# HCPL-7840.net
KiCad netlist of a schematic drawn in EAGLE
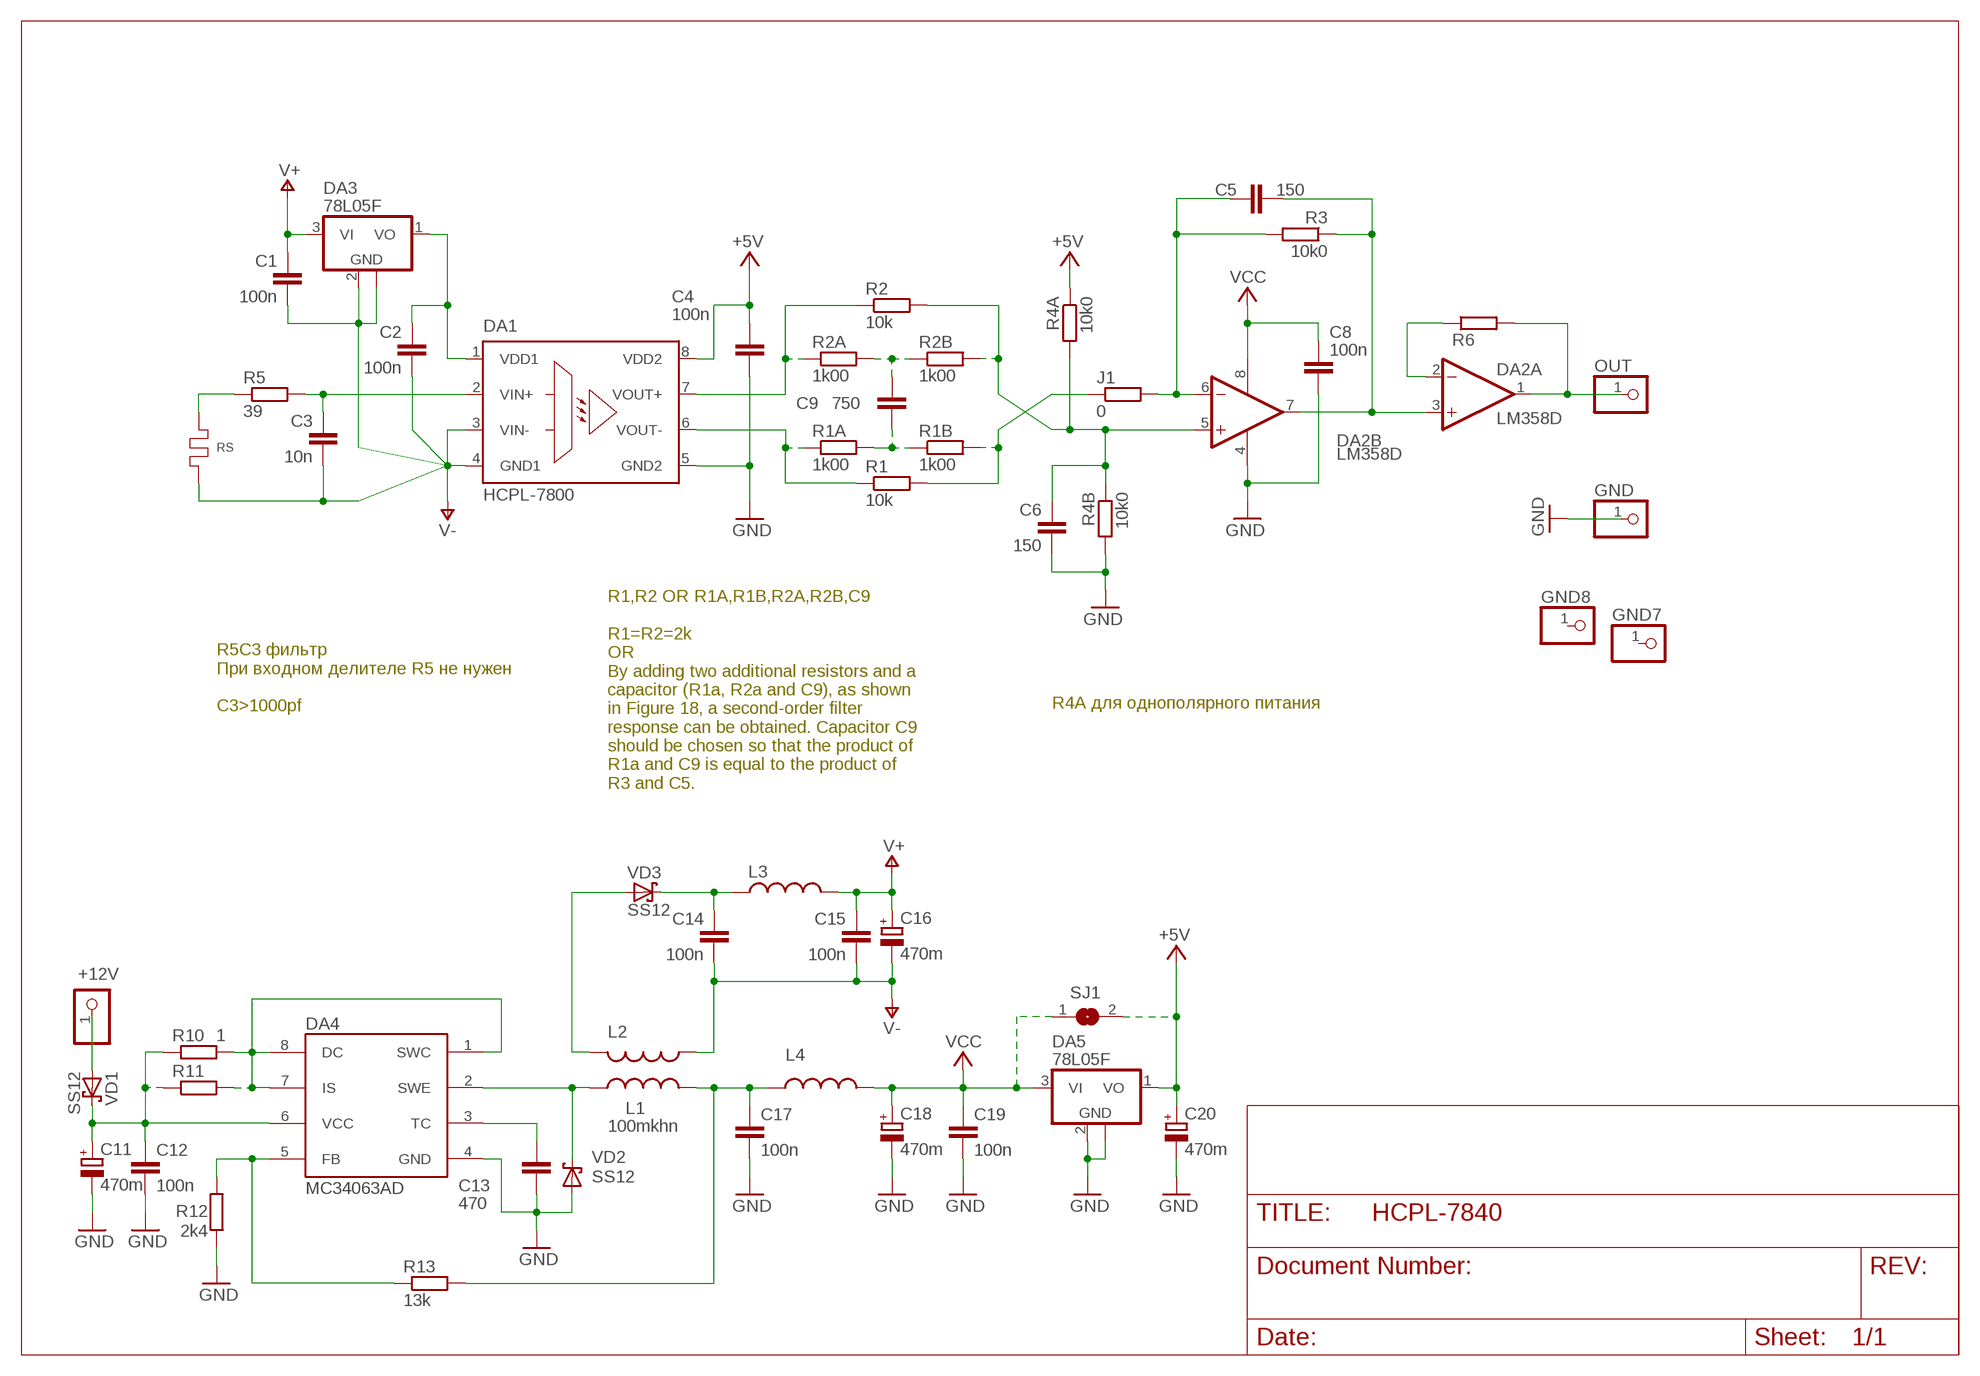
[diagram p0: schematic, sheet 1]

(export (version "E")
  (design (tool "Eeschema 10.0.6"))
  (components
    (comp (ref "+12V")
      (value "PINHD-1X1")
      (footprint "eagle-import:1X01")
      (libsource (lib "eagle-import") (part "PINHD-1X1"))
    )
    (comp (ref "C1")
      (value "100n")
      (footprint "eagle-import:C0805")
      (libsource (lib "eagle-import") (part "C-EUC0805"))
    )
    (comp (ref "C2")
      (value "100n")
      (footprint "eagle-import:C075-032X103")
      (libsource (lib "eagle-import") (part "C-EU075-032X103"))
    )
    (comp (ref "C3")
      (value "10n")
      (footprint "eagle-import:C0805")
      (libsource (lib "eagle-import") (part "C-EUC0805"))
    )
    (comp (ref "C4")
      (value "100n")
      (footprint "eagle-import:C075-032X103")
      (libsource (lib "eagle-import") (part "C-EU075-032X103"))
    )
    (comp (ref "C5")
      (value "150")
      (footprint "eagle-import:C0805")
      (libsource (lib "eagle-import") (part "C-EUC0805"))
    )
    (comp (ref "C6")
      (value "150")
      (footprint "eagle-import:C0805")
      (libsource (lib "eagle-import") (part "C-EUC0805"))
    )
    (comp (ref "C8")
      (value "100n")
      (footprint "eagle-import:C075-032X103")
      (libsource (lib "eagle-import") (part "C-EU075-032X103"))
    )
    (comp (ref "C9")
      (value "750")
      (footprint "eagle-import:C0805")
      (libsource (lib "eagle-import") (part "C-EUC0805"))
    )
    (comp (ref "C11")
      (value "470m")
      (footprint "eagle-import:E2,5-5")
      (libsource (lib "eagle-import") (part "CPOL-EUE2.5-5"))
    )
    (comp (ref "C12")
      (value "100n")
      (footprint "eagle-import:C0805")
      (libsource (lib "eagle-import") (part "C-EUC0805"))
    )
    (comp (ref "C13")
      (value "470")
      (footprint "eagle-import:C0805")
      (libsource (lib "eagle-import") (part "C-EUC0805"))
    )
    (comp (ref "C14")
      (value "100n")
      (footprint "eagle-import:C0805")
      (libsource (lib "eagle-import") (part "C-EUC0805"))
    )
    (comp (ref "C15")
      (value "100n")
      (footprint "eagle-import:C0805")
      (libsource (lib "eagle-import") (part "C-EUC0805"))
    )
    (comp (ref "C16")
      (value "470m")
      (footprint "eagle-import:E2,5-5")
      (libsource (lib "eagle-import") (part "CPOL-EUE2.5-5"))
    )
    (comp (ref "C17")
      (value "100n")
      (footprint "eagle-import:C0805")
      (libsource (lib "eagle-import") (part "C-EUC0805"))
    )
    (comp (ref "C18")
      (value "470m")
      (footprint "eagle-import:E2,5-5")
      (libsource (lib "eagle-import") (part "CPOL-EUE2.5-5"))
    )
    (comp (ref "C19")
      (value "100n")
      (footprint "eagle-import:C0805")
      (libsource (lib "eagle-import") (part "C-EUC0805"))
    )
    (comp (ref "C20")
      (value "470m")
      (footprint "eagle-import:E2,5-5")
      (libsource (lib "eagle-import") (part "CPOL-EUE2.5-5"))
    )
    (comp (ref "DA1")
      (value "HCPL-7800")
      (footprint "eagle-import:DIL08")
      (fields (field (name "MPN") "HCPL-7800A#500"))
      (libsource (lib "eagle-import") (part "HCPL-7800"))
    )
    (comp (ref "DA2")
      (value "LM358D")
      (footprint "eagle-import:SO08")
      (libsource (lib "eagle-import") (part "LM358D"))
    )
    (comp (ref "DA3")
      (value "78L05F")
      (footprint "eagle-import:SOT89")
      (libsource (lib "eagle-import") (part "78LF05"))
    )
    (comp (ref "DA4")
      (value "MC34063AD")
      (footprint "eagle-import:SOIC8")
      (libsource (lib "eagle-import") (part "MC34063AD"))
    )
    (comp (ref "DA5")
      (value "78L05F")
      (footprint "eagle-import:SOT89")
      (libsource (lib "eagle-import") (part "78LF05"))
    )
    (comp (ref "GND")
      (value "PINHD-1X1")
      (footprint "eagle-import:1X01")
      (libsource (lib "eagle-import") (part "PINHD-1X1"))
    )
    (comp (ref "GND7")
      (value "PINHD-1X1")
      (footprint "eagle-import:1X01")
      (libsource (lib "eagle-import") (part "PINHD-1X1"))
    )
    (comp (ref "GND8")
      (value "PINHD-1X1")
      (footprint "eagle-import:1X01")
      (libsource (lib "eagle-import") (part "PINHD-1X1"))
    )
    (comp (ref "J1")
      (value "0")
      (footprint "eagle-import:R1206W")
      (libsource (lib "eagle-import") (part "R-EU_R1206W"))
    )
    (comp (ref "L1")
      (value "100mkhn")
      (footprint "eagle-import:LAN02KR")
      (libsource (lib "eagle-import") (part "L-USLAN02KR"))
    )
    (comp (ref "L2")
      (value "L-USLAN02KR")
      (footprint "eagle-import:LAN02KR")
      (libsource (lib "eagle-import") (part "L-USLAN02KR"))
    )
    (comp (ref "L3")
      (value "L0204/7")
      (footprint "eagle-import:0204_7")
      (libsource (lib "eagle-import") (part "L0204/7"))
    )
    (comp (ref "L4")
      (value "L-US0204/7")
      (footprint "eagle-import:0204_7")
      (libsource (lib "eagle-import") (part "L-US0204/7"))
    )
    (comp (ref "OUT")
      (value "PINHD-1X1")
      (footprint "eagle-import:1X01")
      (libsource (lib "eagle-import") (part "PINHD-1X1"))
    )
    (comp (ref "R1")
      (value "10k")
      (footprint "eagle-import:M0805")
      (libsource (lib "eagle-import") (part "R-EU_M0805"))
    )
    (comp (ref "R1A")
      (value "1k00")
      (footprint "eagle-import:M0805")
      (libsource (lib "eagle-import") (part "R-EU_M0805"))
    )
    (comp (ref "R1B")
      (value "1k00")
      (footprint "eagle-import:M0805")
      (libsource (lib "eagle-import") (part "R-EU_M0805"))
    )
    (comp (ref "R2")
      (value "10k")
      (footprint "eagle-import:M0805")
      (libsource (lib "eagle-import") (part "R-EU_M0805"))
    )
    (comp (ref "R2A")
      (value "1k00")
      (footprint "eagle-import:M0805")
      (libsource (lib "eagle-import") (part "R-EU_M0805"))
    )
    (comp (ref "R2B")
      (value "1k00")
      (footprint "eagle-import:M0805")
      (libsource (lib "eagle-import") (part "R-EU_M0805"))
    )
    (comp (ref "R3")
      (value "10k0")
      (footprint "eagle-import:M0805")
      (libsource (lib "eagle-import") (part "R-EU_M0805"))
    )
    (comp (ref "R4A")
      (value "10k0")
      (footprint "eagle-import:M0805")
      (libsource (lib "eagle-import") (part "R-EU_M0805"))
    )
    (comp (ref "R4B")
      (value "10k0")
      (footprint "eagle-import:M0805")
      (libsource (lib "eagle-import") (part "R-EU_M0805"))
    )
    (comp (ref "R5")
      (value "39")
      (footprint "eagle-import:M0805")
      (libsource (lib "eagle-import") (part "R-EU_M0805"))
    )
    (comp (ref "R6")
      (value "R-EU_M0805")
      (footprint "eagle-import:M0805")
      (libsource (lib "eagle-import") (part "R-EU_M0805"))
    )
    (comp (ref "R10")
      (value "1")
      (footprint "eagle-import:M1206")
      (libsource (lib "eagle-import") (part "R-EU_M1206"))
    )
    (comp (ref "R11")
      (value "R-EU_M1206")
      (footprint "eagle-import:M1206")
      (libsource (lib "eagle-import") (part "R-EU_M1206"))
    )
    (comp (ref "R12")
      (value "2k4")
      (footprint "eagle-import:M0805")
      (libsource (lib "eagle-import") (part "R-EU_M0805"))
    )
    (comp (ref "R13")
      (value "13k")
      (footprint "eagle-import:0207_10")
      (libsource (lib "eagle-import") (part "R-EU_0207/10"))
    )
    (comp (ref "RS") (value "R") (footprint "eagle-import:75ШС") (libsource (lib "eagle-import") (part "R")))
    (comp (ref "SJ1") (value "SJ") (footprint "eagle-import:SJ") (libsource (lib "eagle-import") (part "SJ")))
    (comp (ref "VD1")
      (value "SS12")
      (footprint "eagle-import:SMB")
      (libsource (lib "eagle-import") (part "SCHOTTKY-DIODESMD"))
    )
    (comp (ref "VD2")
      (value "SS12")
      (footprint "eagle-import:SMB")
      (libsource (lib "eagle-import") (part "SCHOTTKY-DIODESMD"))
    )
    (comp (ref "VD3")
      (value "SS12")
      (footprint "eagle-import:SMB")
      (libsource (lib "eagle-import") (part "SCHOTTKY-DIODESMD"))
    )
  )
  (nets
    (net (code "1") (name "+5V") (class "Default")
      (node (ref "C20") (pin "+") (pinfunction "+_+") (pintype "passive"))
      (node (ref "C4") (pin "1") (pinfunction "1_1") (pintype "passive"))
      (node (ref "DA1") (pin "8") (pinfunction "VDD2_8") (pintype "power_in"))
      (node (ref "DA5") (pin "1") (pinfunction "VO_1") (pintype "passive"))
      (node (ref "R4A") (pin "1") (pinfunction "1_1") (pintype "passive"))
      (node (ref "SJ1") (pin "2") (pinfunction "2_2") (pintype "passive"))
    )
    (net (code "2") (name "GND") (class "Default")
      (node (ref "C11") (pin "-") (pinfunction "-_-") (pintype "passive"))
      (node (ref "C12") (pin "2") (pinfunction "2_2") (pintype "passive"))
      (node (ref "C13") (pin "2") (pinfunction "2_2") (pintype "passive"))
      (node (ref "C17") (pin "2") (pinfunction "2_2") (pintype "passive"))
      (node (ref "C18") (pin "-") (pinfunction "-_-") (pintype "passive"))
      (node (ref "C19") (pin "2") (pinfunction "2_2") (pintype "passive"))
      (node (ref "C20") (pin "-") (pinfunction "-_-") (pintype "passive"))
      (node (ref "C4") (pin "2") (pinfunction "2_2") (pintype "passive"))
      (node (ref "C6") (pin "2") (pinfunction "2_2") (pintype "passive"))
      (node (ref "C8") (pin "2") (pinfunction "2_2") (pintype "passive"))
      (node (ref "DA1") (pin "5") (pinfunction "GND2_5") (pintype "power_in"))
      (node (ref "DA2") (pin "4") (pinfunction "V-_4") (pintype "power_in"))
      (node (ref "DA4") (pin "4") (pinfunction "GND_4") (pintype "passive"))
      (node (ref "DA5") (pin "2") (pinfunction "GND_2") (pintype "passive"))
      (node (ref "DA5") (pin "2@1") (pinfunction "GND_2@1") (pintype "passive"))
      (node (ref "GND") (pin "1") (pinfunction "1_1") (pintype "passive"))
      (node (ref "R12") (pin "1") (pinfunction "1_1") (pintype "passive"))
      (node (ref "R4B") (pin "2") (pinfunction "2_2") (pintype "passive"))
      (node (ref "VD2") (pin "A") (pinfunction "A_A") (pintype "passive"))
    )
    (net (code "3") (name "Net-(+12V-Pad1)") (class "Default")
      (node (ref "+12V") (pin "1") (pinfunction "1_1") (pintype "passive"))
      (node (ref "VD1") (pin "A") (pinfunction "A_A") (pintype "passive"))
    )
    (net (code "4") (name "Net-(C9-Pad1)") (class "Default")
      (node (ref "C9") (pin "1") (pinfunction "1_1") (pintype "passive"))
      (node (ref "R2A") (pin "2") (pinfunction "2_2") (pintype "passive"))
      (node (ref "R2B") (pin "1") (pinfunction "1_1") (pintype "passive"))
    )
    (net (code "5") (name "Net-(C9-Pad2)") (class "Default")
      (node (ref "C9") (pin "2") (pinfunction "2_2") (pintype "passive"))
      (node (ref "R1A") (pin "2") (pinfunction "2_2") (pintype "passive"))
      (node (ref "R1B") (pin "1") (pinfunction "1_1") (pintype "passive"))
    )
    (net (code "6") (name "Net-(C14-Pad1)") (class "Default")
      (node (ref "C14") (pin "1") (pinfunction "1_1") (pintype "passive"))
      (node (ref "L3") (pin "1") (pinfunction "1_1") (pintype "passive"))
      (node (ref "VD3") (pin "C") (pinfunction "C_C") (pintype "passive"))
    )
    (net (code "7") (name "Net-(C17-Pad1)") (class "Default")
      (node (ref "C17") (pin "1") (pinfunction "1_1") (pintype "passive"))
      (node (ref "L1") (pin "2") (pinfunction "2_2") (pintype "passive"))
      (node (ref "L4") (pin "1") (pinfunction "1_1") (pintype "passive"))
      (node (ref "R13") (pin "2") (pinfunction "2_2") (pintype "passive"))
    )
    (net (code "8") (name "Net-(DA1-VDD1)") (class "Default")
      (node (ref "C2") (pin "1") (pinfunction "1_1") (pintype "passive"))
      (node (ref "DA1") (pin "1") (pinfunction "VDD1_1") (pintype "power_in"))
      (node (ref "DA3") (pin "1") (pinfunction "VO_1") (pintype "passive"))
    )
    (net (code "9") (name "Net-(DA1-VIN+)") (class "Default")
      (node (ref "C3") (pin "1") (pinfunction "1_1") (pintype "passive"))
      (node (ref "DA1") (pin "2") (pinfunction "VIN+_2") (pintype "power_in"))
      (node (ref "R5") (pin "2") (pinfunction "2_2") (pintype "passive"))
    )
    (net (code "10") (name "Net-(DA1-VOUT+)") (class "Default")
      (node (ref "DA1") (pin "7") (pinfunction "VOUT+_7") (pintype "power_in"))
      (node (ref "R2") (pin "1") (pinfunction "1_1") (pintype "passive"))
      (node (ref "R2A") (pin "1") (pinfunction "1_1") (pintype "passive"))
    )
    (net (code "11") (name "Net-(DA1-VOUT-)") (class "Default")
      (node (ref "DA1") (pin "6") (pinfunction "VOUT-_6") (pintype "power_in"))
      (node (ref "R1") (pin "1") (pinfunction "1_1") (pintype "passive"))
      (node (ref "R1A") (pin "1") (pinfunction "1_1") (pintype "passive"))
    )
    (net (code "12") (name "Net-(DA2A-+IN)") (class "Default")
      (node (ref "C5") (pin "2") (pinfunction "2_2") (pintype "passive"))
      (node (ref "DA2") (pin "3") (pinfunction "+IN_3") (pintype "input"))
      (node (ref "DA2") (pin "7") (pinfunction "OUT_7") (pintype "output"))
      (node (ref "R3") (pin "1") (pinfunction "1_1") (pintype "passive"))
    )
    (net (code "13") (name "Net-(DA2A--IN)") (class "Default")
      (node (ref "DA2") (pin "2") (pinfunction "-IN_2") (pintype "input"))
      (node (ref "R6") (pin "1") (pinfunction "1_1") (pintype "passive"))
    )
    (net (code "14") (name "Net-(DA2A-OUT)") (class "Default")
      (node (ref "DA2") (pin "1") (pinfunction "OUT_1") (pintype "output"))
      (node (ref "OUT") (pin "1") (pinfunction "1_1") (pintype "passive"))
      (node (ref "R6") (pin "2") (pinfunction "2_2") (pintype "passive"))
    )
    (net (code "15") (name "Net-(DA2B-+IN)") (class "Default")
      (node (ref "C6") (pin "1") (pinfunction "1_1") (pintype "passive"))
      (node (ref "DA2") (pin "5") (pinfunction "+IN_5") (pintype "input"))
      (node (ref "R2") (pin "2") (pinfunction "2_2") (pintype "passive"))
      (node (ref "R2B") (pin "2") (pinfunction "2_2") (pintype "passive"))
      (node (ref "R4A") (pin "2") (pinfunction "2_2") (pintype "passive"))
      (node (ref "R4B") (pin "1") (pinfunction "1_1") (pintype "passive"))
    )
    (net (code "16") (name "Net-(DA2B--IN)") (class "Default")
      (node (ref "C5") (pin "1") (pinfunction "1_1") (pintype "passive"))
      (node (ref "DA2") (pin "6") (pinfunction "-IN_6") (pintype "input"))
      (node (ref "J1") (pin "2") (pinfunction "2_2") (pintype "passive"))
      (node (ref "R3") (pin "2") (pinfunction "2_2") (pintype "passive"))
    )
    (net (code "17") (name "Net-(DA4-DC)") (class "Default")
      (node (ref "DA4") (pin "1") (pinfunction "SWC_1") (pintype "passive"))
      (node (ref "DA4") (pin "7") (pinfunction "IS_7") (pintype "passive"))
      (node (ref "DA4") (pin "8") (pinfunction "DC_8") (pintype "passive"))
      (node (ref "R10") (pin "2") (pinfunction "2_2") (pintype "passive"))
      (node (ref "R11") (pin "2") (pinfunction "2_2") (pintype "passive"))
    )
    (net (code "18") (name "Net-(DA4-FB)") (class "Default")
      (node (ref "DA4") (pin "5") (pinfunction "FB_5") (pintype "passive"))
      (node (ref "R12") (pin "2") (pinfunction "2_2") (pintype "passive"))
      (node (ref "R13") (pin "1") (pinfunction "1_1") (pintype "passive"))
    )
    (net (code "19") (name "Net-(DA4-SWE)") (class "Default")
      (node (ref "DA4") (pin "2") (pinfunction "SWE_2") (pintype "passive"))
      (node (ref "L1") (pin "1") (pinfunction "1_1") (pintype "passive"))
      (node (ref "VD2") (pin "C") (pinfunction "C_C") (pintype "passive"))
    )
    (net (code "20") (name "Net-(DA4-TC)") (class "Default")
      (node (ref "C13") (pin "1") (pinfunction "1_1") (pintype "passive"))
      (node (ref "DA4") (pin "3") (pinfunction "TC_3") (pintype "passive"))
    )
    (net (code "21") (name "Net-(DA4-VCC)") (class "Default")
      (node (ref "C11") (pin "+") (pinfunction "+_+") (pintype "passive"))
      (node (ref "C12") (pin "1") (pinfunction "1_1") (pintype "passive"))
      (node (ref "DA4") (pin "6") (pinfunction "VCC_6") (pintype "passive"))
      (node (ref "R10") (pin "1") (pinfunction "1_1") (pintype "passive"))
      (node (ref "R11") (pin "1") (pinfunction "1_1") (pintype "passive"))
      (node (ref "VD1") (pin "C") (pinfunction "C_C") (pintype "passive"))
    )
    (net (code "22") (name "Net-(J1-Pad1)") (class "Default")
      (node (ref "J1") (pin "1") (pinfunction "1_1") (pintype "passive"))
      (node (ref "R1") (pin "2") (pinfunction "2_2") (pintype "passive"))
      (node (ref "R1B") (pin "2") (pinfunction "2_2") (pintype "passive"))
    )
    (net (code "23") (name "Net-(L2-Pad1)") (class "Default")
      (node (ref "L2") (pin "1") (pinfunction "1_1") (pintype "passive"))
      (node (ref "VD3") (pin "A") (pinfunction "A_A") (pintype "passive"))
    )
    (net (code "24") (name "Net-(R5-Pad1)") (class "Default")
      (node (ref "R5") (pin "1") (pinfunction "1_1") (pintype "passive"))
      (node (ref "RS") (pin "P$2") (pinfunction "P$2_P$2") (pintype "bidirectional"))
    )
    (net (code "25") (name "V+") (class "Default")
      (node (ref "C1") (pin "1") (pinfunction "1_1") (pintype "passive"))
      (node (ref "C15") (pin "1") (pinfunction "1_1") (pintype "passive"))
      (node (ref "C16") (pin "+") (pinfunction "+_+") (pintype "passive"))
      (node (ref "DA3") (pin "3") (pinfunction "VI_3") (pintype "input"))
      (node (ref "L3") (pin "2") (pinfunction "2_2") (pintype "passive"))
    )
    (net (code "26") (name "V-") (class "Default")
      (node (ref "C1") (pin "2") (pinfunction "2_2") (pintype "passive"))
      (node (ref "C14") (pin "2") (pinfunction "2_2") (pintype "passive"))
      (node (ref "C15") (pin "2") (pinfunction "2_2") (pintype "passive"))
      (node (ref "C16") (pin "-") (pinfunction "-_-") (pintype "passive"))
      (node (ref "C2") (pin "2") (pinfunction "2_2") (pintype "passive"))
      (node (ref "C3") (pin "2") (pinfunction "2_2") (pintype "passive"))
      (node (ref "DA1") (pin "3") (pinfunction "VIN-_3") (pintype "power_in"))
      (node (ref "DA1") (pin "4") (pinfunction "GND1_4") (pintype "power_in"))
      (node (ref "DA3") (pin "2") (pinfunction "GND_2") (pintype "passive"))
      (node (ref "DA3") (pin "2@1") (pinfunction "GND_2@1") (pintype "passive"))
      (node (ref "L2") (pin "2") (pinfunction "2_2") (pintype "passive"))
      (node (ref "RS") (pin "P$1") (pinfunction "P$1_P$1") (pintype "bidirectional"))
    )
    (net (code "27") (name "VCC") (class "Default")
      (node (ref "C18") (pin "+") (pinfunction "+_+") (pintype "passive"))
      (node (ref "C19") (pin "1") (pinfunction "1_1") (pintype "passive"))
      (node (ref "C8") (pin "1") (pinfunction "1_1") (pintype "passive"))
      (node (ref "DA2") (pin "8") (pinfunction "V+_8") (pintype "power_in"))
      (node (ref "DA5") (pin "3") (pinfunction "VI_3") (pintype "input"))
      (node (ref "L4") (pin "2") (pinfunction "2_2") (pintype "passive"))
      (node (ref "SJ1") (pin "1") (pinfunction "1_1") (pintype "passive"))
    )
    (net (code "28") (name "unconnected-(GND7-Pad1)") (class "Default")
      (node (ref "GND7") (pin "1") (pinfunction "1_1") (pintype "passive"))
    )
    (net (code "29") (name "unconnected-(GND8-Pad1)") (class "Default")
      (node (ref "GND8") (pin "1") (pinfunction "1_1") (pintype "passive"))
    )
  )
)
